# heliostat.net
KiCad netlist of a schematic drawn in EAGLE
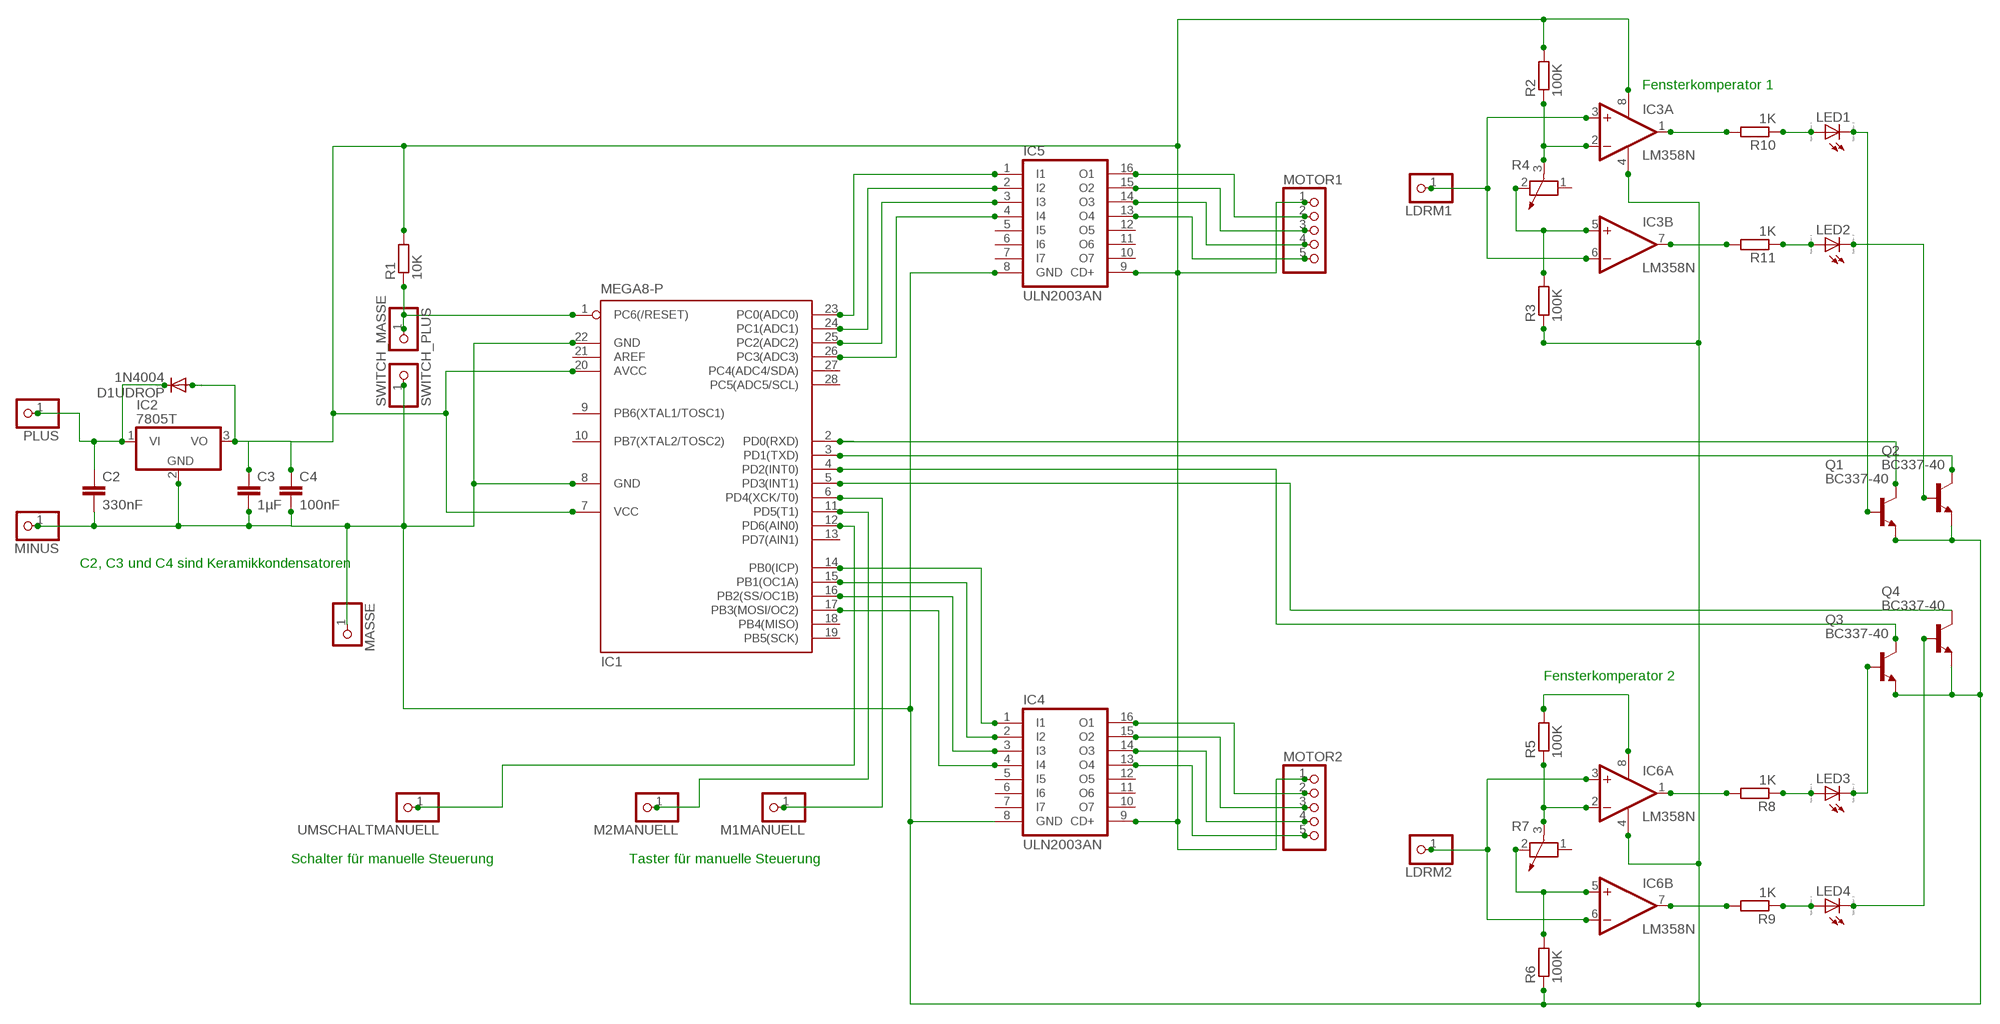
[diagram p0: schematic, sheet 1]

(export (version "E")
  (design (tool "Eeschema 10.0.6"))
  (components
    (comp (ref "C2")
      (value "330nF")
      (footprint "eagle-import:C025-024X044")
      (libsource (lib "eagle-import") (part "C-EU025-024X044"))
    )
    (comp (ref "C3")
      (value "1µF")
      (footprint "eagle-import:C025-024X044")
      (libsource (lib "eagle-import") (part "C-EU025-024X044"))
    )
    (comp (ref "C4")
      (value "100nF")
      (footprint "eagle-import:C025-024X044")
      (libsource (lib "eagle-import") (part "C-EU025-024X044"))
    )
    (comp (ref "D1UDROP")
      (value "1N4004")
      (footprint "eagle-import:DO41-10")
      (libsource (lib "eagle-import") (part "1N4004"))
    )
    (comp (ref "IC1")
      (value "MEGA8-P")
      (footprint "eagle-import:DIL28-3")
      (libsource (lib "eagle-import") (part "MEGA8-P"))
    )
    (comp (ref "IC2")
      (value "7805T")
      (footprint "eagle-import:TO220H")
      (libsource (lib "eagle-import") (part "78T05"))
    )
    (comp (ref "IC3")
      (value "LM358N")
      (footprint "eagle-import:DIL08")
      (libsource (lib "eagle-import") (part "LM358N"))
    )
    (comp (ref "IC4")
      (value "ULN2003AN")
      (footprint "eagle-import:DIL16")
      (libsource (lib "eagle-import") (part "ULN2003AN"))
    )
    (comp (ref "IC5")
      (value "ULN2003AN")
      (footprint "eagle-import:DIL16")
      (libsource (lib "eagle-import") (part "ULN2003AN"))
    )
    (comp (ref "IC6")
      (value "LM358N")
      (footprint "eagle-import:DIL08")
      (libsource (lib "eagle-import") (part "LM358N"))
    )
    (comp (ref "LDRM1")
      (value "PINHD-1X1")
      (footprint "eagle-import:1X01")
      (libsource (lib "eagle-import") (part "PINHD-1X1"))
    )
    (comp (ref "LDRM2")
      (value "PINHD-1X1")
      (footprint "eagle-import:1X01")
      (libsource (lib "eagle-import") (part "PINHD-1X1"))
    )
    (comp (ref "LED1")
      (value "LED_ELD260")
      (footprint "eagle-import:LED_LD260")
      (libsource (lib "eagle-import") (part "LED_ELD260"))
    )
    (comp (ref "LED2")
      (value "LED_ELD260")
      (footprint "eagle-import:LED_LD260")
      (libsource (lib "eagle-import") (part "LED_ELD260"))
    )
    (comp (ref "LED3")
      (value "LED_ELD260")
      (footprint "eagle-import:LED_LD260")
      (libsource (lib "eagle-import") (part "LED_ELD260"))
    )
    (comp (ref "LED4")
      (value "LED_ELD260")
      (footprint "eagle-import:LED_LD260")
      (libsource (lib "eagle-import") (part "LED_ELD260"))
    )
    (comp (ref "M1MANUELL")
      (value "PINHD-1X1")
      (footprint "eagle-import:1X01")
      (libsource (lib "eagle-import") (part "PINHD-1X1"))
    )
    (comp (ref "M2MANUELL")
      (value "PINHD-1X1")
      (footprint "eagle-import:1X01")
      (libsource (lib "eagle-import") (part "PINHD-1X1"))
    )
    (comp (ref "MASSE")
      (value "PINHD-1X1")
      (footprint "eagle-import:1X01")
      (libsource (lib "eagle-import") (part "PINHD-1X1"))
    )
    (comp (ref "MINUS")
      (value "PINHD-1X1")
      (footprint "eagle-import:1X01")
      (libsource (lib "eagle-import") (part "PINHD-1X1"))
    )
    (comp (ref "MOTOR1")
      (value "PINHD-1X5")
      (footprint "eagle-import:1X05")
      (libsource (lib "eagle-import") (part "PINHD-1X5"))
    )
    (comp (ref "MOTOR2")
      (value "PINHD-1X5")
      (footprint "eagle-import:1X05")
      (libsource (lib "eagle-import") (part "PINHD-1X5"))
    )
    (comp (ref "PLUS")
      (value "PINHD-1X1")
      (footprint "eagle-import:1X01")
      (libsource (lib "eagle-import") (part "PINHD-1X1"))
    )
    (comp (ref "Q1")
      (value "BC337-40")
      (footprint "eagle-import:TO92")
      (libsource (lib "eagle-import") (part "BC337-40"))
    )
    (comp (ref "Q2")
      (value "BC337-40")
      (footprint "eagle-import:TO92")
      (libsource (lib "eagle-import") (part "BC337-40"))
    )
    (comp (ref "Q3")
      (value "BC337-40")
      (footprint "eagle-import:TO92")
      (libsource (lib "eagle-import") (part "BC337-40"))
    )
    (comp (ref "Q4")
      (value "BC337-40")
      (footprint "eagle-import:TO92")
      (libsource (lib "eagle-import") (part "BC337-40"))
    )
    (comp (ref "R1")
      (value "10K")
      (footprint "eagle-import:0204V")
      (libsource (lib "eagle-import") (part "R-EU_0204/2V"))
    )
    (comp (ref "R2")
      (value "100K")
      (footprint "eagle-import:0204V")
      (libsource (lib "eagle-import") (part "R-EU_0204/2V"))
    )
    (comp (ref "R3")
      (value "100K")
      (footprint "eagle-import:0204V")
      (libsource (lib "eagle-import") (part "R-EU_0204/2V"))
    )
    (comp (ref "R4")
      (value "POTENTIOMETER_PT-10")
      (footprint "eagle-import:PT-10")
      (libsource (lib "eagle-import") (part "POTENTIOMETER_PT-10"))
    )
    (comp (ref "R5")
      (value "100K")
      (footprint "eagle-import:0204V")
      (libsource (lib "eagle-import") (part "R-EU_0204/2V"))
    )
    (comp (ref "R6")
      (value "100K")
      (footprint "eagle-import:0204V")
      (libsource (lib "eagle-import") (part "R-EU_0204/2V"))
    )
    (comp (ref "R7")
      (value "POTENTIOMETER_PT-10")
      (footprint "eagle-import:PT-10")
      (libsource (lib "eagle-import") (part "POTENTIOMETER_PT-10"))
    )
    (comp (ref "R8")
      (value "1K")
      (footprint "eagle-import:0204V")
      (libsource (lib "eagle-import") (part "R-EU_0204/2V"))
    )
    (comp (ref "R9")
      (value "1K")
      (footprint "eagle-import:0204V")
      (libsource (lib "eagle-import") (part "R-EU_0204/2V"))
    )
    (comp (ref "R10")
      (value "1K")
      (footprint "eagle-import:0204V")
      (libsource (lib "eagle-import") (part "R-EU_0204/2V"))
    )
    (comp (ref "R11")
      (value "1K")
      (footprint "eagle-import:0204V")
      (libsource (lib "eagle-import") (part "R-EU_0204/2V"))
    )
    (comp (ref "SWITCH_MASSE")
      (value "PINHD-1X1")
      (footprint "eagle-import:1X01")
      (libsource (lib "eagle-import") (part "PINHD-1X1"))
    )
    (comp (ref "SWITCH_PLUS")
      (value "PINHD-1X1")
      (footprint "eagle-import:1X01")
      (libsource (lib "eagle-import") (part "PINHD-1X1"))
    )
    (comp (ref "UMSCHALTMANUELL")
      (value "PINHD-1X1")
      (footprint "eagle-import:1X01")
      (libsource (lib "eagle-import") (part "PINHD-1X1"))
    )
  )
  (nets
    (net (code "1") (name "Net-(IC1-AVCC)") (class "Default")
      (node (ref "C3") (pin "1") (pinfunction "1_1") (pintype "passive"))
      (node (ref "C4") (pin "1") (pinfunction "1_1") (pintype "passive"))
      (node (ref "D1UDROP") (pin "A") (pinfunction "A_A") (pintype "passive"))
      (node (ref "IC1") (pin "20") (pinfunction "AVCC_20") (pintype "power_in"))
      (node (ref "IC1") (pin "7") (pinfunction "VCC_7") (pintype "power_in"))
      (node (ref "IC2") (pin "3") (pinfunction "VO_3") (pintype "passive"))
      (node (ref "IC3") (pin "8") (pinfunction "V+_8") (pintype "power_in"))
      (node (ref "IC4") (pin "9") (pinfunction "CD+_9") (pintype "passive"))
      (node (ref "IC5") (pin "9") (pinfunction "CD+_9") (pintype "passive"))
      (node (ref "MOTOR1") (pin "1") (pinfunction "1_1") (pintype "passive"))
      (node (ref "MOTOR2") (pin "1") (pinfunction "1_1") (pintype "passive"))
      (node (ref "R1") (pin "2") (pinfunction "2_2") (pintype "passive"))
      (node (ref "R2") (pin "2") (pinfunction "2_2") (pintype "passive"))
    )
    (net (code "2") (name "Net-(IC1-PB0(ICP))") (class "Default")
      (node (ref "IC1") (pin "14") (pinfunction "PB0(ICP)_14") (pintype "bidirectional"))
      (node (ref "IC4") (pin "1") (pinfunction "I1_1") (pintype "input"))
    )
    (net (code "3") (name "Net-(IC1-PB1(OC1A))") (class "Default")
      (node (ref "IC1") (pin "15") (pinfunction "PB1(OC1A)_15") (pintype "bidirectional"))
      (node (ref "IC4") (pin "2") (pinfunction "I2_2") (pintype "input"))
    )
    (net (code "4") (name "Net-(IC1-PB2(SS{slash}OC1B))") (class "Default")
      (node (ref "IC1") (pin "16") (pinfunction "PB2(SS/OC1B)_16") (pintype "bidirectional"))
      (node (ref "IC4") (pin "3") (pinfunction "I3_3") (pintype "input"))
    )
    (net (code "5") (name "Net-(IC1-PB3(MOSI{slash}OC2))") (class "Default")
      (node (ref "IC1") (pin "17") (pinfunction "PB3(MOSI/OC2)_17") (pintype "bidirectional"))
      (node (ref "IC4") (pin "4") (pinfunction "I4_4") (pintype "input"))
    )
    (net (code "6") (name "Net-(IC1-PC0(ADC0))") (class "Default")
      (node (ref "IC1") (pin "23") (pinfunction "PC0(ADC0)_23") (pintype "bidirectional"))
      (node (ref "IC5") (pin "1") (pinfunction "I1_1") (pintype "input"))
    )
    (net (code "7") (name "Net-(IC1-PC1(ADC1))") (class "Default")
      (node (ref "IC1") (pin "24") (pinfunction "PC1(ADC1)_24") (pintype "bidirectional"))
      (node (ref "IC5") (pin "2") (pinfunction "I2_2") (pintype "input"))
    )
    (net (code "8") (name "Net-(IC1-PC2(ADC2))") (class "Default")
      (node (ref "IC1") (pin "25") (pinfunction "PC2(ADC2)_25") (pintype "bidirectional"))
      (node (ref "IC5") (pin "3") (pinfunction "I3_3") (pintype "input"))
    )
    (net (code "9") (name "Net-(IC1-PC3(ADC3))") (class "Default")
      (node (ref "IC1") (pin "26") (pinfunction "PC3(ADC3)_26") (pintype "bidirectional"))
      (node (ref "IC5") (pin "4") (pinfunction "I4_4") (pintype "input"))
    )
    (net (code "10") (name "Net-(IC1-PC6({slash}RESET))") (class "Default")
      (node (ref "IC1") (pin "1") (pinfunction "PC6(/RESET)_1") (pintype "bidirectional"))
      (node (ref "R1") (pin "1") (pinfunction "1_1") (pintype "passive"))
      (node (ref "SWITCH_PLUS") (pin "1") (pinfunction "1_1") (pintype "passive"))
    )
    (net (code "11") (name "Net-(IC1-PD0(RXD))") (class "Default")
      (node (ref "IC1") (pin "2") (pinfunction "PD0(RXD)_2") (pintype "bidirectional"))
      (node (ref "Q1") (pin "3") (pinfunction "C_3") (pintype "passive"))
    )
    (net (code "12") (name "Net-(IC1-PD1(TXD))") (class "Default")
      (node (ref "IC1") (pin "3") (pinfunction "PD1(TXD)_3") (pintype "bidirectional"))
      (node (ref "Q2") (pin "3") (pinfunction "C_3") (pintype "passive"))
    )
    (net (code "13") (name "Net-(IC1-PD2(INT0))") (class "Default")
      (node (ref "IC1") (pin "4") (pinfunction "PD2(INT0)_4") (pintype "bidirectional"))
      (node (ref "Q3") (pin "3") (pinfunction "C_3") (pintype "passive"))
    )
    (net (code "14") (name "Net-(IC1-PD3(INT1))") (class "Default")
      (node (ref "IC1") (pin "5") (pinfunction "PD3(INT1)_5") (pintype "bidirectional"))
      (node (ref "Q4") (pin "3") (pinfunction "C_3") (pintype "passive"))
    )
    (net (code "15") (name "Net-(IC1-PD4(XCK{slash}T0))") (class "Default")
      (node (ref "IC1") (pin "6") (pinfunction "PD4(XCK/T0)_6") (pintype "bidirectional"))
      (node (ref "M1MANUELL") (pin "1") (pinfunction "1_1") (pintype "passive"))
    )
    (net (code "16") (name "Net-(IC1-PD5(T1))") (class "Default")
      (node (ref "IC1") (pin "11") (pinfunction "PD5(T1)_11") (pintype "bidirectional"))
      (node (ref "M2MANUELL") (pin "1") (pinfunction "1_1") (pintype "passive"))
    )
    (net (code "17") (name "Net-(IC1-PD6(AIN0))") (class "Default")
      (node (ref "IC1") (pin "12") (pinfunction "PD6(AIN0)_12") (pintype "bidirectional"))
      (node (ref "UMSCHALTMANUELL") (pin "1") (pinfunction "1_1") (pintype "passive"))
    )
    (net (code "18") (name "Net-(IC2-GND)") (class "Default")
      (node (ref "C2") (pin "2") (pinfunction "2_2") (pintype "passive"))
      (node (ref "C3") (pin "2") (pinfunction "2_2") (pintype "passive"))
      (node (ref "C4") (pin "2") (pinfunction "2_2") (pintype "passive"))
      (node (ref "IC1") (pin "22") (pinfunction "GND_22") (pintype "power_in"))
      (node (ref "IC1") (pin "8") (pinfunction "GND_8") (pintype "power_in"))
      (node (ref "IC2") (pin "2") (pinfunction "GND_2") (pintype "passive"))
      (node (ref "IC3") (pin "4") (pinfunction "V-_4") (pintype "power_in"))
      (node (ref "IC4") (pin "8") (pinfunction "GND_8") (pintype "power_in"))
      (node (ref "IC5") (pin "8") (pinfunction "GND_8") (pintype "power_in"))
      (node (ref "IC6") (pin "4") (pinfunction "V-_4") (pintype "power_in"))
      (node (ref "MASSE") (pin "1") (pinfunction "1_1") (pintype "passive"))
      (node (ref "MINUS") (pin "1") (pinfunction "1_1") (pintype "passive"))
      (node (ref "Q1") (pin "1") (pinfunction "E_1") (pintype "passive"))
      (node (ref "Q2") (pin "1") (pinfunction "E_1") (pintype "passive"))
      (node (ref "Q3") (pin "1") (pinfunction "E_1") (pintype "passive"))
      (node (ref "Q4") (pin "1") (pinfunction "E_1") (pintype "passive"))
      (node (ref "R3") (pin "1") (pinfunction "1_1") (pintype "passive"))
      (node (ref "R6") (pin "1") (pinfunction "1_1") (pintype "passive"))
      (node (ref "SWITCH_MASSE") (pin "1") (pinfunction "1_1") (pintype "passive"))
    )
    (net (code "19") (name "Net-(IC2-VI)") (class "Default")
      (node (ref "C2") (pin "1") (pinfunction "1_1") (pintype "passive"))
      (node (ref "D1UDROP") (pin "C") (pinfunction "C_C") (pintype "passive"))
      (node (ref "IC2") (pin "1") (pinfunction "VI_1") (pintype "input"))
      (node (ref "PLUS") (pin "1") (pinfunction "1_1") (pintype "passive"))
    )
    (net (code "20") (name "Net-(IC3A-+IN)") (class "Default")
      (node (ref "IC3") (pin "3") (pinfunction "+IN_3") (pintype "input"))
      (node (ref "IC3") (pin "6") (pinfunction "-IN_6") (pintype "input"))
      (node (ref "LDRM1") (pin "1") (pinfunction "1_1") (pintype "passive"))
    )
    (net (code "21") (name "Net-(IC3A--IN)") (class "Default")
      (node (ref "IC3") (pin "2") (pinfunction "-IN_2") (pintype "input"))
      (node (ref "R2") (pin "1") (pinfunction "1_1") (pintype "passive"))
      (node (ref "R4") (pin "3") (pinfunction "3_3") (pintype "passive"))
    )
    (net (code "22") (name "Net-(IC3A-OUT)") (class "Default")
      (node (ref "IC3") (pin "1") (pinfunction "OUT_1") (pintype "output"))
      (node (ref "R10") (pin "2") (pinfunction "2_2") (pintype "passive"))
    )
    (net (code "23") (name "Net-(IC3B-+IN)") (class "Default")
      (node (ref "IC3") (pin "5") (pinfunction "+IN_5") (pintype "input"))
      (node (ref "R3") (pin "2") (pinfunction "2_2") (pintype "passive"))
      (node (ref "R4") (pin "2") (pinfunction "2_2") (pintype "passive"))
    )
    (net (code "24") (name "Net-(IC3B-OUT)") (class "Default")
      (node (ref "IC3") (pin "7") (pinfunction "OUT_7") (pintype "output"))
      (node (ref "R11") (pin "2") (pinfunction "2_2") (pintype "passive"))
    )
    (net (code "25") (name "Net-(IC4-O1)") (class "Default")
      (node (ref "IC4") (pin "16") (pinfunction "O1_16") (pintype "open_collector"))
      (node (ref "MOTOR2") (pin "2") (pinfunction "2_2") (pintype "passive"))
    )
    (net (code "26") (name "Net-(IC4-O2)") (class "Default")
      (node (ref "IC4") (pin "15") (pinfunction "O2_15") (pintype "open_collector"))
      (node (ref "MOTOR2") (pin "3") (pinfunction "3_3") (pintype "passive"))
    )
    (net (code "27") (name "Net-(IC4-O3)") (class "Default")
      (node (ref "IC4") (pin "14") (pinfunction "O3_14") (pintype "open_collector"))
      (node (ref "MOTOR2") (pin "4") (pinfunction "4_4") (pintype "passive"))
    )
    (net (code "28") (name "Net-(IC4-O4)") (class "Default")
      (node (ref "IC4") (pin "13") (pinfunction "O4_13") (pintype "open_collector"))
      (node (ref "MOTOR2") (pin "5") (pinfunction "5_5") (pintype "passive"))
    )
    (net (code "29") (name "Net-(IC5-O1)") (class "Default")
      (node (ref "IC5") (pin "16") (pinfunction "O1_16") (pintype "open_collector"))
      (node (ref "MOTOR1") (pin "2") (pinfunction "2_2") (pintype "passive"))
    )
    (net (code "30") (name "Net-(IC5-O2)") (class "Default")
      (node (ref "IC5") (pin "15") (pinfunction "O2_15") (pintype "open_collector"))
      (node (ref "MOTOR1") (pin "3") (pinfunction "3_3") (pintype "passive"))
    )
    (net (code "31") (name "Net-(IC5-O3)") (class "Default")
      (node (ref "IC5") (pin "14") (pinfunction "O3_14") (pintype "open_collector"))
      (node (ref "MOTOR1") (pin "4") (pinfunction "4_4") (pintype "passive"))
    )
    (net (code "32") (name "Net-(IC5-O4)") (class "Default")
      (node (ref "IC5") (pin "13") (pinfunction "O4_13") (pintype "open_collector"))
      (node (ref "MOTOR1") (pin "5") (pinfunction "5_5") (pintype "passive"))
    )
    (net (code "33") (name "Net-(IC6A-+IN)") (class "Default")
      (node (ref "IC6") (pin "3") (pinfunction "+IN_3") (pintype "input"))
      (node (ref "IC6") (pin "6") (pinfunction "-IN_6") (pintype "input"))
      (node (ref "LDRM2") (pin "1") (pinfunction "1_1") (pintype "passive"))
    )
    (net (code "34") (name "Net-(IC6A--IN)") (class "Default")
      (node (ref "IC6") (pin "2") (pinfunction "-IN_2") (pintype "input"))
      (node (ref "R5") (pin "1") (pinfunction "1_1") (pintype "passive"))
      (node (ref "R7") (pin "3") (pinfunction "3_3") (pintype "passive"))
    )
    (net (code "35") (name "Net-(IC6A-OUT)") (class "Default")
      (node (ref "IC6") (pin "1") (pinfunction "OUT_1") (pintype "output"))
      (node (ref "R8") (pin "2") (pinfunction "2_2") (pintype "passive"))
    )
    (net (code "36") (name "Net-(IC6B-+IN)") (class "Default")
      (node (ref "IC6") (pin "5") (pinfunction "+IN_5") (pintype "input"))
      (node (ref "R6") (pin "2") (pinfunction "2_2") (pintype "passive"))
      (node (ref "R7") (pin "2") (pinfunction "2_2") (pintype "passive"))
    )
    (net (code "37") (name "Net-(IC6B-OUT)") (class "Default")
      (node (ref "IC6") (pin "7") (pinfunction "OUT_7") (pintype "output"))
      (node (ref "R9") (pin "2") (pinfunction "2_2") (pintype "passive"))
    )
    (net (code "38") (name "Net-(IC6C-V+)") (class "Default")
      (node (ref "IC6") (pin "8") (pinfunction "V+_8") (pintype "power_in"))
      (node (ref "R5") (pin "2") (pinfunction "2_2") (pintype "passive"))
    )
    (net (code "39") (name "Net-(LED1-C)") (class "Default")
      (node (ref "LED1") (pin "K") (pinfunction "C_K") (pintype "passive"))
      (node (ref "Q1") (pin "2") (pinfunction "B_2") (pintype "passive"))
    )
    (net (code "40") (name "Net-(LED1-PadA)") (class "Default")
      (node (ref "LED1") (pin "A") (pinfunction "A_A") (pintype "passive"))
      (node (ref "R10") (pin "1") (pinfunction "1_1") (pintype "passive"))
    )
    (net (code "41") (name "Net-(LED2-C)") (class "Default")
      (node (ref "LED2") (pin "K") (pinfunction "C_K") (pintype "passive"))
      (node (ref "Q2") (pin "2") (pinfunction "B_2") (pintype "passive"))
    )
    (net (code "42") (name "Net-(LED2-PadA)") (class "Default")
      (node (ref "LED2") (pin "A") (pinfunction "A_A") (pintype "passive"))
      (node (ref "R11") (pin "1") (pinfunction "1_1") (pintype "passive"))
    )
    (net (code "43") (name "Net-(LED3-C)") (class "Default")
      (node (ref "LED3") (pin "K") (pinfunction "C_K") (pintype "passive"))
      (node (ref "Q3") (pin "2") (pinfunction "B_2") (pintype "passive"))
    )
    (net (code "44") (name "Net-(LED3-PadA)") (class "Default")
      (node (ref "LED3") (pin "A") (pinfunction "A_A") (pintype "passive"))
      (node (ref "R8") (pin "1") (pinfunction "1_1") (pintype "passive"))
    )
    (net (code "45") (name "Net-(LED4-C)") (class "Default")
      (node (ref "LED4") (pin "K") (pinfunction "C_K") (pintype "passive"))
      (node (ref "Q4") (pin "2") (pinfunction "B_2") (pintype "passive"))
    )
    (net (code "46") (name "Net-(LED4-PadA)") (class "Default")
      (node (ref "LED4") (pin "A") (pinfunction "A_A") (pintype "passive"))
      (node (ref "R9") (pin "1") (pinfunction "1_1") (pintype "passive"))
    )
    (net (code "47") (name "unconnected-(IC1-AREF-Pad21)") (class "Default")
      (node (ref "IC1") (pin "21") (pinfunction "AREF_21") (pintype "passive"))
    )
    (net (code "48") (name "unconnected-(IC1-PB4(MISO)-Pad18)") (class "Default")
      (node (ref "IC1") (pin "18") (pinfunction "PB4(MISO)_18") (pintype "bidirectional"))
    )
    (net (code "49") (name "unconnected-(IC1-PB5(SCK)-Pad19)") (class "Default")
      (node (ref "IC1") (pin "19") (pinfunction "PB5(SCK)_19") (pintype "bidirectional"))
    )
    (net (code "50") (name "unconnected-(IC1-PB6(XTAL1{slash}TOSC1)-Pad9)") (class "Default")
      (node (ref "IC1") (pin "9") (pinfunction "PB6(XTAL1/TOSC1)_9") (pintype "bidirectional"))
    )
    (net (code "51") (name "unconnected-(IC1-PB7(XTAL2{slash}TOSC2)-Pad10)") (class "Default")
      (node (ref "IC1") (pin "10") (pinfunction "PB7(XTAL2/TOSC2)_10") (pintype "bidirectional"))
    )
    (net (code "52") (name "unconnected-(IC1-PC4(ADC4{slash}SDA)-Pad27)") (class "Default")
      (node (ref "IC1") (pin "27") (pinfunction "PC4(ADC4/SDA)_27") (pintype "bidirectional"))
    )
    (net (code "53") (name "unconnected-(IC1-PC5(ADC5{slash}SCL)-Pad28)") (class "Default")
      (node (ref "IC1") (pin "28") (pinfunction "PC5(ADC5/SCL)_28") (pintype "bidirectional"))
    )
    (net (code "54") (name "unconnected-(IC1-PD7(AIN1)-Pad13)") (class "Default")
      (node (ref "IC1") (pin "13") (pinfunction "PD7(AIN1)_13") (pintype "bidirectional"))
    )
    (net (code "55") (name "unconnected-(IC4-I5-Pad5)") (class "Default")
      (node (ref "IC4") (pin "5") (pinfunction "I5_5") (pintype "input"))
    )
    (net (code "56") (name "unconnected-(IC4-I6-Pad6)") (class "Default")
      (node (ref "IC4") (pin "6") (pinfunction "I6_6") (pintype "input"))
    )
    (net (code "57") (name "unconnected-(IC4-I7-Pad7)") (class "Default")
      (node (ref "IC4") (pin "7") (pinfunction "I7_7") (pintype "input"))
    )
    (net (code "58") (name "unconnected-(IC4-O5-Pad12)") (class "Default")
      (node (ref "IC4") (pin "12") (pinfunction "O5_12") (pintype "open_collector"))
    )
    (net (code "59") (name "unconnected-(IC4-O6-Pad11)") (class "Default")
      (node (ref "IC4") (pin "11") (pinfunction "O6_11") (pintype "open_collector"))
    )
    (net (code "60") (name "unconnected-(IC4-O7-Pad10)") (class "Default")
      (node (ref "IC4") (pin "10") (pinfunction "O7_10") (pintype "open_collector"))
    )
    (net (code "61") (name "unconnected-(IC5-I5-Pad5)") (class "Default")
      (node (ref "IC5") (pin "5") (pinfunction "I5_5") (pintype "input"))
    )
    (net (code "62") (name "unconnected-(IC5-I6-Pad6)") (class "Default")
      (node (ref "IC5") (pin "6") (pinfunction "I6_6") (pintype "input"))
    )
    (net (code "63") (name "unconnected-(IC5-I7-Pad7)") (class "Default")
      (node (ref "IC5") (pin "7") (pinfunction "I7_7") (pintype "input"))
    )
    (net (code "64") (name "unconnected-(IC5-O5-Pad12)") (class "Default")
      (node (ref "IC5") (pin "12") (pinfunction "O5_12") (pintype "open_collector"))
    )
    (net (code "65") (name "unconnected-(IC5-O6-Pad11)") (class "Default")
      (node (ref "IC5") (pin "11") (pinfunction "O6_11") (pintype "open_collector"))
    )
    (net (code "66") (name "unconnected-(IC5-O7-Pad10)") (class "Default")
      (node (ref "IC5") (pin "10") (pinfunction "O7_10") (pintype "open_collector"))
    )
    (net (code "67") (name "unconnected-(R4-Pad1)") (class "Default")
      (node (ref "R4") (pin "1") (pinfunction "1_1") (pintype "passive"))
    )
    (net (code "68") (name "unconnected-(R7-Pad1)") (class "Default")
      (node (ref "R7") (pin "1") (pinfunction "1_1") (pintype "passive"))
    )
  )
)
